# ColorSS_v2_SCH.net
KiCad netlist of a schematic drawn in Altium Designer
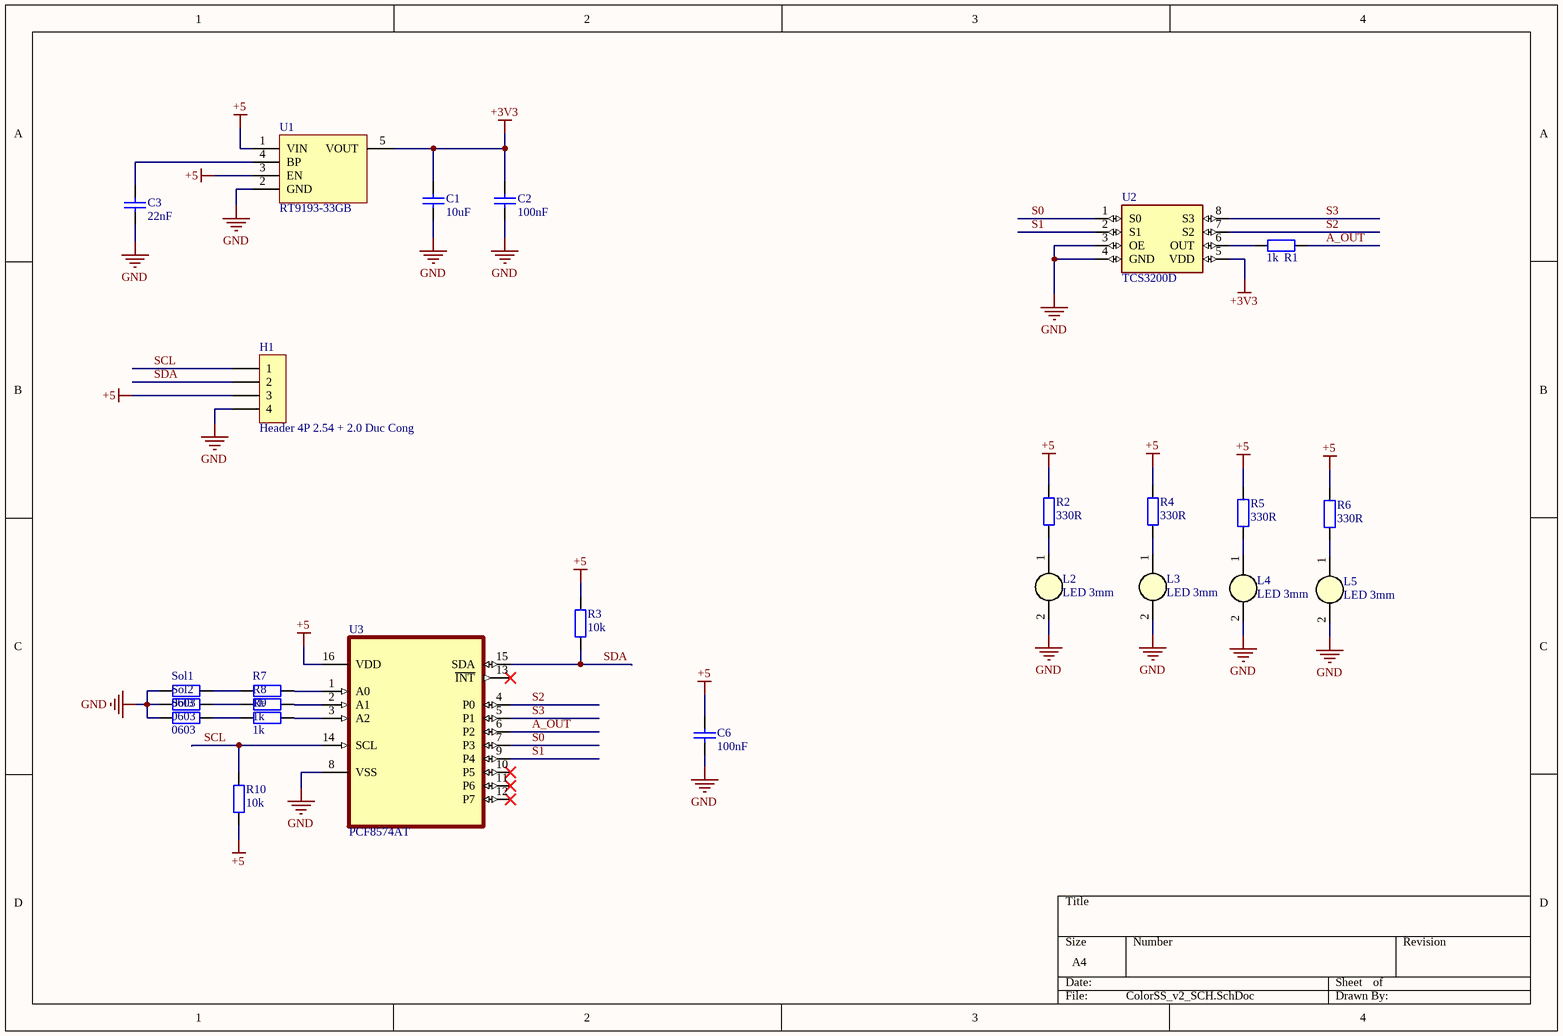
[diagram p0: ColorSS_v2_SCH.SchDoc]

(export (version "E")
  (design (tool "Eeschema 10.0.6"))
  (components
    (comp (ref "C1")
      (value "10uF")
      (footprint "tu 0603")
      (description "Dán")
      (libsource (lib "namnt_Lib") (part "Tu 0603 106 16V 20%"))
    )
    (comp (ref "C2")
      (value "100nF")
      (footprint "tu 0603")
      (description "Dán")
      (libsource (lib "namnt_Lib") (part "Tu 0603 104 50V 10%"))
    )
    (comp (ref "C3")
      (value "22nF")
      (footprint "tu 0603")
      (description "Dán")
      (libsource (lib "namnt_Lib") (part "Tu 0603 104 50V 10%"))
    )
    (comp (ref "C6")
      (value "100nF")
      (footprint "tu 0603")
      (description "Dán")
      (libsource (lib "namnt_Lib") (part "Tu 0603 104 50V 10%"))
    )
    (comp (ref "H1")
      (value "Header 4P 2.54 + 2.0 Duc Cong")
      (footprint "Header 4P DC 2.54 + 2.0")
      (description "Cắm")
      (libsource (lib "namnt_Lib") (part "Header 4P 2.54 + 2.0 Duc Cong"))
    )
    (comp (ref "L2")
      (value "LED 3mm")
      (footprint "LED-3MM-WHITE")
      (description "Cắm")
      (libsource (lib "namnt_Lib") (part "LED 3mm Trang"))
    )
    (comp (ref "L3")
      (value "LED 3mm")
      (footprint "LED-3MM-WHITE")
      (description "Cắm")
      (libsource (lib "namnt_Lib") (part "LED 3mm Trang"))
    )
    (comp (ref "L4")
      (value "LED 3mm")
      (footprint "LED-3MM-WHITE")
      (description "Cắm")
      (libsource (lib "namnt_Lib") (part "LED 3mm Trang"))
    )
    (comp (ref "L5")
      (value "LED 3mm")
      (footprint "LED-3MM-WHITE")
      (description "Cắm")
      (libsource (lib "namnt_Lib") (part "LED 3mm Trang"))
    )
    (comp (ref "R1")
      (value "1k")
      (footprint "tro smd 0603")
      (description "Dán")
      (libsource (lib "namnt_Lib") (part "Tro 0603 1% 1k"))
    )
    (comp (ref "R2")
      (value "330R")
      (footprint "tro smd 0603")
      (description "Dán")
      (libsource (lib "namnt_Lib") (part "Tro 0603 5% 330R"))
    )
    (comp (ref "R3")
      (value "10k")
      (footprint "tro smd 0603")
      (description "Dán")
      (libsource (lib "namnt_Lib") (part "Tro 0603 5% 330R"))
    )
    (comp (ref "R4")
      (value "330R")
      (footprint "tro smd 0603")
      (description "Dán")
      (libsource (lib "namnt_Lib") (part "Tro 0603 5% 330R"))
    )
    (comp (ref "R5")
      (value "330R")
      (footprint "tro smd 0603")
      (description "Dán")
      (libsource (lib "namnt_Lib") (part "Tro 0603 5% 330R"))
    )
    (comp (ref "R6")
      (value "330R")
      (footprint "tro smd 0603")
      (description "Dán")
      (libsource (lib "namnt_Lib") (part "Tro 0603 5% 330R"))
    )
    (comp (ref "R7")
      (value "1k")
      (footprint "tro smd 0603")
      (description "Dán")
      (libsource (lib "namnt_Lib") (part "Tro 0603 1% 1k"))
    )
    (comp (ref "R8")
      (value "1k")
      (footprint "tro smd 0603")
      (description "Dán")
      (libsource (lib "namnt_Lib") (part "Tro 0603 1% 1k"))
    )
    (comp (ref "R9")
      (value "1k")
      (footprint "tro smd 0603")
      (description "Dán")
      (libsource (lib "namnt_Lib") (part "Tro 0603 1% 1k"))
    )
    (comp (ref "R10")
      (value "10k")
      (footprint "tro smd 0603")
      (description "Dán")
      (libsource (lib "namnt_Lib") (part "Tro 0603 5% 330R"))
    )
    (comp (ref "Sol1")
      (value "0603")
      (footprint "Solder 0603")
      (description "Dán")
      (libsource (lib "namnt_Lib") (part "Solder 0603"))
    )
    (comp (ref "Sol2")
      (value "0603")
      (footprint "Solder 0603")
      (description "Dán")
      (libsource (lib "namnt_Lib") (part "Solder 0603"))
    )
    (comp (ref "Sol3")
      (value "0603")
      (footprint "Solder 0603")
      (description "Dán")
      (libsource (lib "namnt_Lib") (part "Solder 0603"))
    )
    (comp (ref "U1")
      (value "RT9193-33GB")
      (footprint "SOT23-5")
      (description "Linear Voltage Regulator IC 1 Output 300mA SOT-23-5")
      (fields (field (name "MANUFACTURER") "Richtek USA Inc."))
      (libsource (lib "namnt_Lib") (part "REG_5.5V-3.3V-0.3A-1W-SOT-23-5"))
    )
    (comp (ref "U2")
      (value "TCS3200D")
      (footprint "SOIC8")
      (description "Color Sensor - Auto Power Down 8-SOIC (0.154, 3.90mm Width)")
      (fields (field (name "MF") "ams"))
      (libsource (lib "namnt_Lib") (part "TCS3200D"))
    )
    (comp (ref "U3")
      (value "PCF8574AT")
      (footprint "SOIC127P1032X265-16N")
      (description "IÂ²C Bus IC Operating temperature: -40...+85 Â°C Power supply: 2.5...6 V Package: SO-16W")
      (fields (field (name "MF") "NXP USA"))
      (libsource (lib "namnt_Lib") (part "PCF8574AT"))
    )
  )
  (nets
    (net (code "1") (name "+3V3") (class "Default")
      (node (ref "C1") (pin "1") (pinfunction "1_1") (pintype "passive"))
      (node (ref "C2") (pin "1") (pinfunction "1_1") (pintype "passive"))
      (node (ref "U1") (pin "5") (pinfunction "VOUT_5") (pintype "passive"))
      (node (ref "U2") (pin "5") (pinfunction "VDD_5") (pintype "bidirectional"))
    )
    (net (code "2") (name "+5") (class "Default")
      (node (ref "C6") (pin "1") (pinfunction "1_1") (pintype "passive"))
      (node (ref "H1") (pin "3") (pinfunction "3_3") (pintype "passive"))
      (node (ref "R10") (pin "2") (pinfunction "2_2") (pintype "passive"))
      (node (ref "R2") (pin "2") (pinfunction "2_2") (pintype "passive"))
      (node (ref "R3") (pin "2") (pinfunction "2_2") (pintype "passive"))
      (node (ref "R4") (pin "2") (pinfunction "2_2") (pintype "passive"))
      (node (ref "R5") (pin "2") (pinfunction "2_2") (pintype "passive"))
      (node (ref "R6") (pin "2") (pinfunction "2_2") (pintype "passive"))
      (node (ref "U1") (pin "1") (pinfunction "VIN_1") (pintype "passive"))
      (node (ref "U1") (pin "3") (pinfunction "EN_3") (pintype "passive"))
      (node (ref "U3") (pin "16") (pinfunction "VDD_16") (pintype "power_in"))
    )
    (net (code "3") (name "/A_OUT") (class "Default")
      (node (ref "R1") (pin "2") (pinfunction "2_2") (pintype "passive"))
      (node (ref "U3") (pin "6") (pinfunction "P2_6") (pintype "bidirectional"))
    )
    (net (code "4") (name "/S0") (class "Default")
      (node (ref "U2") (pin "1") (pinfunction "S0_1") (pintype "bidirectional"))
      (node (ref "U3") (pin "7") (pinfunction "P3_7") (pintype "bidirectional"))
    )
    (net (code "5") (name "/S1") (class "Default")
      (node (ref "U2") (pin "2") (pinfunction "S1_2") (pintype "bidirectional"))
      (node (ref "U3") (pin "9") (pinfunction "P4_9") (pintype "bidirectional"))
    )
    (net (code "6") (name "/S2") (class "Default")
      (node (ref "U2") (pin "7") (pinfunction "S2_7") (pintype "bidirectional"))
      (node (ref "U3") (pin "4") (pinfunction "P0_4") (pintype "bidirectional"))
    )
    (net (code "7") (name "/S3") (class "Default")
      (node (ref "U2") (pin "8") (pinfunction "S3_8") (pintype "bidirectional"))
      (node (ref "U3") (pin "5") (pinfunction "P1_5") (pintype "bidirectional"))
    )
    (net (code "8") (name "/SCL") (class "Default")
      (node (ref "H1") (pin "1") (pinfunction "1_1") (pintype "passive"))
      (node (ref "R10") (pin "1") (pinfunction "1_1") (pintype "passive"))
      (node (ref "U3") (pin "14") (pinfunction "SCL_14") (pintype "input"))
    )
    (net (code "9") (name "/SDA") (class "Default")
      (node (ref "H1") (pin "2") (pinfunction "2_2") (pintype "passive"))
      (node (ref "R3") (pin "1") (pinfunction "1_1") (pintype "passive"))
      (node (ref "U3") (pin "15") (pinfunction "SDA_15") (pintype "bidirectional"))
    )
    (net (code "10") (name "GND") (class "Default")
      (node (ref "C1") (pin "2") (pinfunction "2_2") (pintype "passive"))
      (node (ref "C2") (pin "2") (pinfunction "2_2") (pintype "passive"))
      (node (ref "C3") (pin "2") (pinfunction "2_2") (pintype "passive"))
      (node (ref "C6") (pin "2") (pinfunction "2_2") (pintype "passive"))
      (node (ref "H1") (pin "4") (pinfunction "4_4") (pintype "passive"))
      (node (ref "L2") (pin "2") (pinfunction "K_2") (pintype "passive"))
      (node (ref "L3") (pin "2") (pinfunction "K_2") (pintype "passive"))
      (node (ref "L4") (pin "2") (pinfunction "K_2") (pintype "passive"))
      (node (ref "L5") (pin "2") (pinfunction "K_2") (pintype "passive"))
      (node (ref "Sol1") (pin "1") (pinfunction "1_1") (pintype "passive"))
      (node (ref "Sol2") (pin "1") (pinfunction "1_1") (pintype "passive"))
      (node (ref "Sol3") (pin "1") (pinfunction "1_1") (pintype "passive"))
      (node (ref "U1") (pin "2") (pinfunction "GND_2") (pintype "passive"))
      (node (ref "U2") (pin "3") (pinfunction "OE_3") (pintype "bidirectional"))
      (node (ref "U2") (pin "4") (pinfunction "GND_4") (pintype "bidirectional"))
      (node (ref "U3") (pin "8") (pinfunction "VSS_8") (pintype "passive"))
    )
    (net (code "11") (name "Net-(L2-A)") (class "Default")
      (node (ref "L2") (pin "1") (pinfunction "A_1") (pintype "passive"))
      (node (ref "R2") (pin "1") (pinfunction "1_1") (pintype "passive"))
    )
    (net (code "12") (name "Net-(L3-A)") (class "Default")
      (node (ref "L3") (pin "1") (pinfunction "A_1") (pintype "passive"))
      (node (ref "R4") (pin "1") (pinfunction "1_1") (pintype "passive"))
    )
    (net (code "13") (name "Net-(L4-A)") (class "Default")
      (node (ref "L4") (pin "1") (pinfunction "A_1") (pintype "passive"))
      (node (ref "R5") (pin "1") (pinfunction "1_1") (pintype "passive"))
    )
    (net (code "14") (name "Net-(L5-A)") (class "Default")
      (node (ref "L5") (pin "1") (pinfunction "A_1") (pintype "passive"))
      (node (ref "R6") (pin "1") (pinfunction "1_1") (pintype "passive"))
    )
    (net (code "15") (name "Net-(R7-Pad1)") (class "Default")
      (node (ref "R7") (pin "1") (pinfunction "1_1") (pintype "passive"))
      (node (ref "Sol1") (pin "2") (pinfunction "2_2") (pintype "passive"))
    )
    (net (code "16") (name "Net-(R8-Pad1)") (class "Default")
      (node (ref "R8") (pin "1") (pinfunction "1_1") (pintype "passive"))
      (node (ref "Sol2") (pin "2") (pinfunction "2_2") (pintype "passive"))
    )
    (net (code "17") (name "Net-(R9-Pad1)") (class "Default")
      (node (ref "R9") (pin "1") (pinfunction "1_1") (pintype "passive"))
      (node (ref "Sol3") (pin "2") (pinfunction "2_2") (pintype "passive"))
    )
    (net (code "18") (name "Net-(U1-BP)") (class "Default")
      (node (ref "C3") (pin "1") (pinfunction "1_1") (pintype "passive"))
      (node (ref "U1") (pin "4") (pinfunction "BP_4") (pintype "passive"))
    )
    (net (code "19") (name "Net-(U2-OUT)") (class "Default")
      (node (ref "R1") (pin "1") (pinfunction "1_1") (pintype "passive"))
      (node (ref "U2") (pin "6") (pinfunction "OUT_6") (pintype "bidirectional"))
    )
    (net (code "20") (name "Net-(U3-A0)") (class "Default")
      (node (ref "R7") (pin "2") (pinfunction "2_2") (pintype "passive"))
      (node (ref "U3") (pin "1") (pinfunction "A0_1") (pintype "input"))
    )
    (net (code "21") (name "Net-(U3-A1)") (class "Default")
      (node (ref "R8") (pin "2") (pinfunction "2_2") (pintype "passive"))
      (node (ref "U3") (pin "2") (pinfunction "A1_2") (pintype "input"))
    )
    (net (code "22") (name "Net-(U3-A2)") (class "Default")
      (node (ref "R9") (pin "2") (pinfunction "2_2") (pintype "passive"))
      (node (ref "U3") (pin "3") (pinfunction "A2_3") (pintype "input"))
    )
    (net (code "23") (name "unconnected-(U3-P5-Pad10)") (class "Default")
      (node (ref "U3") (pin "10") (pinfunction "P5_10") (pintype "bidirectional+no_connect"))
    )
    (net (code "24") (name "unconnected-(U3-P6-Pad11)") (class "Default")
      (node (ref "U3") (pin "11") (pinfunction "P6_11") (pintype "bidirectional+no_connect"))
    )
    (net (code "25") (name "unconnected-(U3-P7-Pad12)") (class "Default")
      (node (ref "U3") (pin "12") (pinfunction "P7_12") (pintype "bidirectional+no_connect"))
    )
    (net (code "26") (name "unconnected-(U3-~{INT}-Pad13)") (class "Default")
      (node (ref "U3") (pin "13") (pinfunction "~{INT}_13") (pintype "output+no_connect"))
    )
  )
)
